# rizzler-hall-sensor-board.net
KiCad netlist of a schematic drawn in Altium Designer
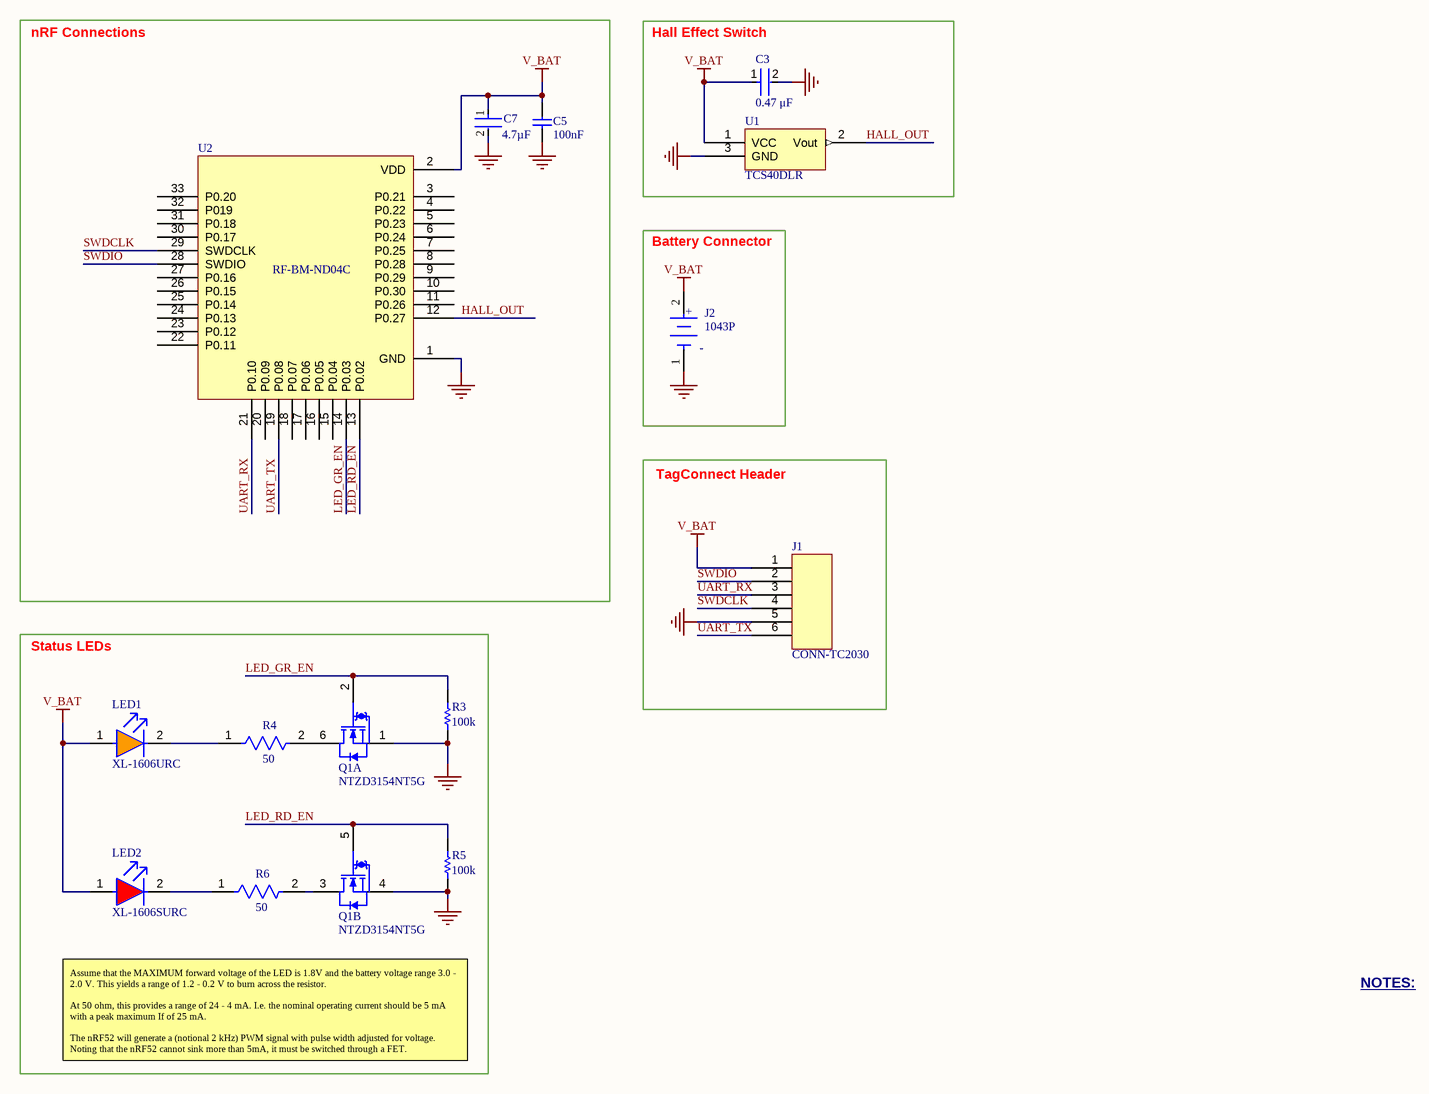
[diagram p0: rizzler-hall-sensor-board.SchDoc]

(export (version "E")
  (design (tool "Eeschema 10.0.6"))
  (components
    (comp (ref "C3")
      (value "0.47 μF")
      (footprint "FP-C0805C-DN-MFG")
      (description "CAP CER 0.47UF 25V X7R 0805")
      (fields (field (name "TOLERANCE") "0.1") (field (name "MANUFACTURER") "KEMET"))
      (libsource (lib "Altium Content Vault") (part "b4654b650e69147ec39a6b967a45e02"))
    )
    (comp (ref "C5")
      (value "100nF")
      (footprint "CAPC0603X03L_C")
      (description "Capacitor, X5R, ±10%")
      (fields (field (name "PART NUMBER") "C0201-100n") (field (name "PUBLISHER") "Nordic Semiconductor"))
      (libsource (lib "lazer-sensor-for-trespassers") (part "CAP"))
    )
    (comp (ref "C7")
      (value "GRM188R61C475KAAJD")
      (footprint "FP-GRM188-0_15-MFG")
      (description "CAP CER 4.7UF 16V X5R 0603")
      (fields (field (name "CAPACITANCE") "4.7µF") (field (name "TOLERANCE") "10%"))
      (libsource (lib "Altium Content Vault") (part "02cd4be3c70576c341d710602a673aa"))
    )
    (comp (ref "J1")
      (value "CONN-TC2030")
      (footprint "TC2030-IDC-PLUG-OF-NAILS-TIGHT")
      (description "TC2030 PLUG-OF-NAILS CABLE")
      (libsource (lib "lazer-sensor-for-trespassers") (part "CONN-TC2030"))
    )
    (comp (ref "J2")
      (value "1043P")
      (footprint "FP-1043P-MFG")
      (description "BATT HOLDER 18650 1 CELL PC PIN")
      (libsource (lib "Altium Content Vault") (part "60d3b5b901a8747834971d0eb8cf3fd"))
    )
    (comp (ref "LED1")
      (value "XL-1606URC")
      (footprint "LED-RA-1606")
      (description "Orange LED 90° mount")
      (libsource (lib "lazer-sensor-for-trespassers") (part "LED-ORANGE-RA"))
    )
    (comp (ref "LED2")
      (value "XL-1606SURC")
      (footprint "LED-RA-1606")
      (description "Red LED 90° mount")
      (libsource (lib "lazer-sensor-for-trespassers") (part "LED-RED-RA"))
    )
    (comp (ref "Q1")
      (value "NTZD3154NT5G")
      (footprint "ONSC-SOT-563-6-463A-01_V")
      (description "Small Signal MOSFET, 20 V, 540 mA, Dual N-Channel, 6-Pin SOT-563, Pb-Free, Tape and Reel")
      (fields (field (name "MANUFACTURER") "On Semiconductor"))
      (libsource (lib "Altium Content Vault") (part "ONSC-NNMOS-6_F"))
    )
    (comp (ref "R3")
      (value "100k")
      (footprint "RESC1005X40X25ML05T10")
      (fields (field (name "PART NUMBER") "RC0402FR-07100KL") (field (name "MANUFACTURER") "Yageo / Phycomp"))
      (libsource (lib "Altium Content Vault") (part "RES"))
    )
    (comp (ref "R4")
      (value "AC0402JR-0750RL")
      (footprint "FP-AC0402-IPC_C")
      (description "RES 50Ω ±5% 0.063W 0402")
      (fields (field (name "TOLERANCE") "5%") (field (name "RESISTANCE") "50"))
      (libsource (lib "Altium Content Vault") (part "1029c3af85768c4190bb7ad29bc67b5"))
    )
    (comp (ref "R5")
      (value "100k")
      (footprint "RESC1005X40X25ML05T10")
      (fields (field (name "PART NUMBER") "RC0402FR-07100KL") (field (name "MANUFACTURER") "Yageo / Phycomp"))
      (libsource (lib "Altium Content Vault") (part "RES"))
    )
    (comp (ref "R6")
      (value "AC0402JR-0750RL")
      (footprint "FP-AC0402-IPC_C")
      (description "RES 50Ω ±5% 0.063W 0402")
      (fields (field (name "TOLERANCE") "5%") (field (name "RESISTANCE") "50"))
      (libsource (lib "Altium Content Vault") (part "1029c3af85768c4190bb7ad29bc67b5"))
    )
    (comp (ref "U1")
      (value "TCS40DLR")
      (footprint "SOT95P245X80-3N")
      (description "Digital-Output Magnetic Sensor (Hall IC). Open drain.")
      (libsource (lib "lazer-sensor-for-trespassers") (part "IC-HALL-TCS40DLR"))
    )
    (comp (ref "U2")
      (value "RF-BM-ND04C")
      (footprint "RF-BM-ND04")
      (description "nRF52810-based Bluetooth 5.0 Low Energy module with internal 32 MHz and 32.768 kHz crystals.")
      (libsource (lib "lazer-sensor-for-trespassers") (part "RF-BM-ND04C"))
    )
  )
  (nets
    (net (code "1") (name "/HALL_OUT") (class "Default")
      (node (ref "U1") (pin "2") (pinfunction "Vout_2") (pintype "output"))
      (node (ref "U2") (pin "12") (pinfunction "P0.27_12") (pintype "passive"))
    )
    (net (code "2") (name "/LED_GR_EN") (class "Default")
      (node (ref "Q1") (pin "2") (pinfunction "G1_2") (pintype "passive"))
      (node (ref "R3") (pin "2") (pinfunction "2_2") (pintype "passive"))
      (node (ref "U2") (pin "14") (pinfunction "P0.03_14") (pintype "passive"))
    )
    (net (code "3") (name "/LED_RD_EN") (class "Default")
      (node (ref "Q1") (pin "5") (pinfunction "G2_5") (pintype "passive"))
      (node (ref "R5") (pin "2") (pinfunction "2_2") (pintype "passive"))
      (node (ref "U2") (pin "13") (pinfunction "P0.02_13") (pintype "passive"))
    )
    (net (code "4") (name "/SWDCLK") (class "Default")
      (node (ref "J1") (pin "4") (pintype "passive"))
      (node (ref "U2") (pin "29") (pinfunction "SWDCLK_29") (pintype "passive"))
    )
    (net (code "5") (name "/SWDIO") (class "Default")
      (node (ref "J1") (pin "2") (pintype "passive"))
      (node (ref "U2") (pin "28") (pinfunction "SWDIO_28") (pintype "passive"))
    )
    (net (code "6") (name "/UART_RX") (class "Default")
      (node (ref "J1") (pin "3") (pintype "passive"))
      (node (ref "U2") (pin "21") (pinfunction "P0.10_21") (pintype "passive"))
    )
    (net (code "7") (name "/UART_TX") (class "Default")
      (node (ref "J1") (pin "6") (pintype "passive"))
      (node (ref "U2") (pin "19") (pinfunction "P0.08_19") (pintype "passive"))
    )
    (net (code "8") (name "GND") (class "Default")
      (node (ref "C3") (pin "2") (pinfunction "2_2") (pintype "passive"))
      (node (ref "C5") (pin "2") (pinfunction "2_2") (pintype "passive"))
      (node (ref "C7") (pin "2") (pinfunction "2_2") (pintype "passive"))
      (node (ref "J1") (pin "5") (pintype "passive"))
      (node (ref "J2") (pin "1") (pinfunction "C_1") (pintype "passive"))
      (node (ref "Q1") (pin "1") (pinfunction "S1_1") (pintype "passive"))
      (node (ref "Q1") (pin "4") (pinfunction "S2_4") (pintype "passive"))
      (node (ref "R3") (pin "1") (pinfunction "1_1") (pintype "passive"))
      (node (ref "R5") (pin "1") (pinfunction "1_1") (pintype "passive"))
      (node (ref "U1") (pin "3") (pinfunction "GND_3") (pintype "power_in"))
      (node (ref "U2") (pin "1") (pinfunction "GND_1") (pintype "passive"))
    )
    (net (code "9") (name "Net-(LED1-C)") (class "Default")
      (node (ref "LED1") (pin "2") (pinfunction "C_2") (pintype "passive"))
      (node (ref "R4") (pin "1") (pinfunction "1_1") (pintype "passive"))
    )
    (net (code "10") (name "Net-(LED2-C)") (class "Default")
      (node (ref "LED2") (pin "2") (pinfunction "C_2") (pintype "passive"))
      (node (ref "R6") (pin "1") (pinfunction "1_1") (pintype "passive"))
    )
    (net (code "11") (name "Net-(Q1A-D1)") (class "Default")
      (node (ref "Q1") (pin "6") (pinfunction "D1_6") (pintype "passive"))
      (node (ref "R4") (pin "2") (pinfunction "2_2") (pintype "passive"))
    )
    (net (code "12") (name "Net-(Q1B-D2)") (class "Default")
      (node (ref "Q1") (pin "3") (pinfunction "D2_3") (pintype "passive"))
      (node (ref "R6") (pin "2") (pinfunction "2_2") (pintype "passive"))
    )
    (net (code "13") (name "V_BAT") (class "Default")
      (node (ref "C3") (pin "1") (pinfunction "1_1") (pintype "passive"))
      (node (ref "C5") (pin "1") (pinfunction "1_1") (pintype "passive"))
      (node (ref "C7") (pin "1") (pinfunction "1_1") (pintype "passive"))
      (node (ref "J1") (pin "1") (pintype "passive"))
      (node (ref "J2") (pin "2") (pinfunction "A_2") (pintype "passive"))
      (node (ref "LED1") (pin "1") (pinfunction "A_1") (pintype "passive"))
      (node (ref "LED2") (pin "1") (pinfunction "A_1") (pintype "passive"))
      (node (ref "U1") (pin "1") (pinfunction "VCC_1") (pintype "power_in"))
      (node (ref "U2") (pin "2") (pinfunction "VDD_2") (pintype "passive"))
    )
    (net (code "14") (name "unconnected-(U2-P0.04-Pad15)") (class "Default")
      (node (ref "U2") (pin "15") (pinfunction "P0.04_15") (pintype "passive"))
    )
    (net (code "15") (name "unconnected-(U2-P0.05-Pad16)") (class "Default")
      (node (ref "U2") (pin "16") (pinfunction "P0.05_16") (pintype "passive"))
    )
    (net (code "16") (name "unconnected-(U2-P0.06-Pad17)") (class "Default")
      (node (ref "U2") (pin "17") (pinfunction "P0.06_17") (pintype "passive"))
    )
    (net (code "17") (name "unconnected-(U2-P0.07-Pad18)") (class "Default")
      (node (ref "U2") (pin "18") (pinfunction "P0.07_18") (pintype "passive"))
    )
    (net (code "18") (name "unconnected-(U2-P0.09-Pad20)") (class "Default")
      (node (ref "U2") (pin "20") (pinfunction "P0.09_20") (pintype "passive"))
    )
    (net (code "19") (name "unconnected-(U2-P0.11-Pad22)") (class "Default")
      (node (ref "U2") (pin "22") (pinfunction "P0.11_22") (pintype "passive"))
    )
    (net (code "20") (name "unconnected-(U2-P0.12-Pad23)") (class "Default")
      (node (ref "U2") (pin "23") (pinfunction "P0.12_23") (pintype "passive"))
    )
    (net (code "21") (name "unconnected-(U2-P0.13-Pad24)") (class "Default")
      (node (ref "U2") (pin "24") (pinfunction "P0.13_24") (pintype "passive"))
    )
    (net (code "22") (name "unconnected-(U2-P0.14-Pad25)") (class "Default")
      (node (ref "U2") (pin "25") (pinfunction "P0.14_25") (pintype "passive"))
    )
    (net (code "23") (name "unconnected-(U2-P0.15-Pad26)") (class "Default")
      (node (ref "U2") (pin "26") (pinfunction "P0.15_26") (pintype "passive"))
    )
    (net (code "24") (name "unconnected-(U2-P0.16-Pad27)") (class "Default")
      (node (ref "U2") (pin "27") (pinfunction "P0.16_27") (pintype "passive"))
    )
    (net (code "25") (name "unconnected-(U2-P0.17-Pad30)") (class "Default")
      (node (ref "U2") (pin "30") (pinfunction "P0.17_30") (pintype "passive"))
    )
    (net (code "26") (name "unconnected-(U2-P0.18-Pad31)") (class "Default")
      (node (ref "U2") (pin "31") (pinfunction "P0.18_31") (pintype "passive"))
    )
    (net (code "27") (name "unconnected-(U2-P0.20-Pad33)") (class "Default")
      (node (ref "U2") (pin "33") (pinfunction "P0.20_33") (pintype "passive"))
    )
    (net (code "28") (name "unconnected-(U2-P0.21-Pad3)") (class "Default")
      (node (ref "U2") (pin "3") (pinfunction "P0.21_3") (pintype "passive"))
    )
    (net (code "29") (name "unconnected-(U2-P0.22-Pad4)") (class "Default")
      (node (ref "U2") (pin "4") (pinfunction "P0.22_4") (pintype "passive"))
    )
    (net (code "30") (name "unconnected-(U2-P0.23-Pad5)") (class "Default")
      (node (ref "U2") (pin "5") (pinfunction "P0.23_5") (pintype "passive"))
    )
    (net (code "31") (name "unconnected-(U2-P0.24-Pad6)") (class "Default")
      (node (ref "U2") (pin "6") (pinfunction "P0.24_6") (pintype "passive"))
    )
    (net (code "32") (name "unconnected-(U2-P0.25-Pad7)") (class "Default")
      (node (ref "U2") (pin "7") (pinfunction "P0.25_7") (pintype "passive"))
    )
    (net (code "33") (name "unconnected-(U2-P0.26-Pad11)") (class "Default")
      (node (ref "U2") (pin "11") (pinfunction "P0.26_11") (pintype "passive"))
    )
    (net (code "34") (name "unconnected-(U2-P0.28-Pad8)") (class "Default")
      (node (ref "U2") (pin "8") (pinfunction "P0.28_8") (pintype "passive"))
    )
    (net (code "35") (name "unconnected-(U2-P0.29-Pad9)") (class "Default")
      (node (ref "U2") (pin "9") (pinfunction "P0.29_9") (pintype "passive"))
    )
    (net (code "36") (name "unconnected-(U2-P0.30-Pad10)") (class "Default")
      (node (ref "U2") (pin "10") (pinfunction "P0.30_10") (pintype "passive"))
    )
    (net (code "37") (name "unconnected-(U2-P019-Pad32)") (class "Default")
      (node (ref "U2") (pin "32") (pinfunction "P019_32") (pintype "passive"))
    )
  )
)
